# ATMEGA848-S52.net
KiCad netlist of a schematic drawn in Altium Designer
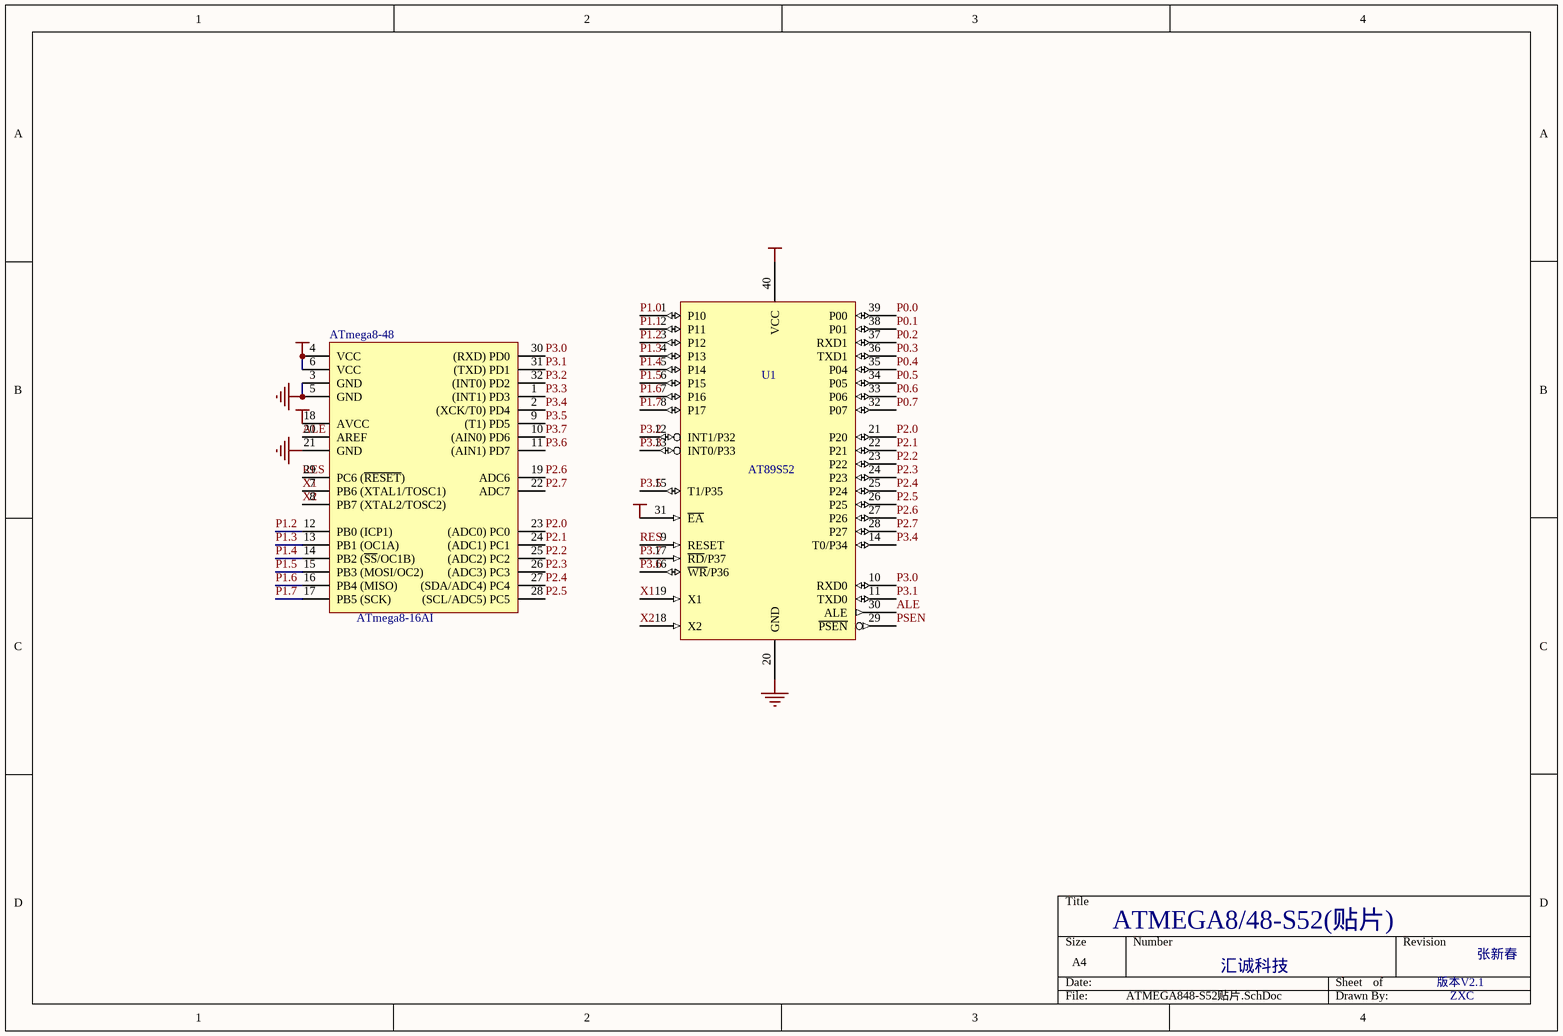
[diagram p0: ATMEGA848-S52贴片.SchDoc]

(export (version "E")
  (design (tool "Eeschema 10.0.6"))
  (components
    (comp (ref "ATmega8-48")
      (value "ATmega8-16AI")
      (footprint "TQFP-32_0.8/7×7mm")
      (description "8 位微处理器/32引脚")
      (fields (field (name "发布者") "磊元工作室"))
      (libsource (lib "微控制处理器") (part "ATmega8-A"))
    )
    (comp (ref "U1") (value "AT89S52") (footprint "DIP-40") (libsource (lib "OldCow1 (2)") (part "8051")))
  )
  (nets
    (net (code "1") (name "/ALE") (class "Default")
      (node (ref "ATmega8-48") (pin "20") (pinfunction "AREF_20") (pintype "passive"))
      (node (ref "U1") (pin "30") (pinfunction "ALE_30") (pintype "output"))
    )
    (net (code "2") (name "/P0.0") (class "Default")
      (node (ref "U1") (pin "39") (pinfunction "P00_39") (pintype "bidirectional"))
    )
    (net (code "3") (name "/P0.1") (class "Default")
      (node (ref "U1") (pin "38") (pinfunction "P01_38") (pintype "bidirectional"))
    )
    (net (code "4") (name "/P0.2") (class "Default")
      (node (ref "U1") (pin "37") (pinfunction "RXD1_37") (pintype "bidirectional"))
    )
    (net (code "5") (name "/P0.3") (class "Default")
      (node (ref "U1") (pin "36") (pinfunction "TXD1_36") (pintype "bidirectional"))
    )
    (net (code "6") (name "/P0.4") (class "Default")
      (node (ref "U1") (pin "35") (pinfunction "P04_35") (pintype "bidirectional"))
    )
    (net (code "7") (name "/P0.5") (class "Default")
      (node (ref "U1") (pin "34") (pinfunction "P05_34") (pintype "bidirectional"))
    )
    (net (code "8") (name "/P0.6") (class "Default")
      (node (ref "U1") (pin "33") (pinfunction "P06_33") (pintype "bidirectional"))
    )
    (net (code "9") (name "/P0.7") (class "Default")
      (node (ref "U1") (pin "32") (pinfunction "P07_32") (pintype "bidirectional"))
    )
    (net (code "10") (name "/P1.0") (class "Default")
      (node (ref "U1") (pin "1") (pinfunction "P10_1") (pintype "bidirectional"))
    )
    (net (code "11") (name "/P1.1") (class "Default")
      (node (ref "U1") (pin "2") (pinfunction "P11_2") (pintype "bidirectional"))
    )
    (net (code "12") (name "/P1.2") (class "Default")
      (node (ref "ATmega8-48") (pin "12") (pinfunction "PB0_(ICP1)_12") (pintype "passive"))
      (node (ref "U1") (pin "3") (pinfunction "P12_3") (pintype "bidirectional"))
    )
    (net (code "13") (name "/P1.3") (class "Default")
      (node (ref "ATmega8-48") (pin "13") (pinfunction "PB1_(OC1A)_13") (pintype "passive"))
      (node (ref "U1") (pin "4") (pinfunction "P13_4") (pintype "bidirectional"))
    )
    (net (code "14") (name "/P1.4") (class "Default")
      (node (ref "ATmega8-48") (pin "14") (pinfunction "PB2_(~{SS}/OC1B)_14") (pintype "passive"))
      (node (ref "U1") (pin "5") (pinfunction "P14_5") (pintype "bidirectional"))
    )
    (net (code "15") (name "/P1.5") (class "Default")
      (node (ref "ATmega8-48") (pin "15") (pinfunction "PB3_(MOSI/OC2)_15") (pintype "passive"))
      (node (ref "U1") (pin "6") (pinfunction "P15_6") (pintype "bidirectional"))
    )
    (net (code "16") (name "/P1.6") (class "Default")
      (node (ref "ATmega8-48") (pin "16") (pinfunction "PB4_(MISO)_16") (pintype "passive"))
      (node (ref "U1") (pin "7") (pinfunction "P16_7") (pintype "bidirectional"))
    )
    (net (code "17") (name "/P1.7") (class "Default")
      (node (ref "ATmega8-48") (pin "17") (pinfunction "PB5_(SCK)_17") (pintype "passive"))
      (node (ref "U1") (pin "8") (pinfunction "P17_8") (pintype "bidirectional"))
    )
    (net (code "18") (name "/P2.0") (class "Default")
      (node (ref "ATmega8-48") (pin "23") (pinfunction "(ADC0)_PC0_23") (pintype "passive"))
      (node (ref "U1") (pin "21") (pinfunction "P20_21") (pintype "bidirectional"))
    )
    (net (code "19") (name "/P2.1") (class "Default")
      (node (ref "ATmega8-48") (pin "24") (pinfunction "(ADC1)_PC1_24") (pintype "passive"))
      (node (ref "U1") (pin "22") (pinfunction "P21_22") (pintype "bidirectional"))
    )
    (net (code "20") (name "/P2.2") (class "Default")
      (node (ref "ATmega8-48") (pin "25") (pinfunction "(ADC2)_PC2_25") (pintype "passive"))
      (node (ref "U1") (pin "23") (pinfunction "P22_23") (pintype "bidirectional"))
    )
    (net (code "21") (name "/P2.3") (class "Default")
      (node (ref "ATmega8-48") (pin "26") (pinfunction "(ADC3)_PC3_26") (pintype "passive"))
      (node (ref "U1") (pin "24") (pinfunction "P23_24") (pintype "bidirectional"))
    )
    (net (code "22") (name "/P2.4") (class "Default")
      (node (ref "ATmega8-48") (pin "27") (pinfunction "(SDA/ADC4)_PC4_27") (pintype "passive"))
      (node (ref "U1") (pin "25") (pinfunction "P24_25") (pintype "bidirectional"))
    )
    (net (code "23") (name "/P2.5") (class "Default")
      (node (ref "ATmega8-48") (pin "28") (pinfunction "(SCL/ADC5)_PC5_28") (pintype "passive"))
      (node (ref "U1") (pin "26") (pinfunction "P25_26") (pintype "bidirectional"))
    )
    (net (code "24") (name "/P2.6") (class "Default")
      (node (ref "ATmega8-48") (pin "19") (pinfunction "ADC6_19") (pintype "passive"))
      (node (ref "U1") (pin "27") (pinfunction "P26_27") (pintype "bidirectional"))
    )
    (net (code "25") (name "/P2.7") (class "Default")
      (node (ref "ATmega8-48") (pin "22") (pinfunction "ADC7_22") (pintype "passive"))
      (node (ref "U1") (pin "28") (pinfunction "P27_28") (pintype "bidirectional"))
    )
    (net (code "26") (name "/P3.0") (class "Default")
      (node (ref "ATmega8-48") (pin "30") (pinfunction "(RXD)_PD0_30") (pintype "passive"))
      (node (ref "U1") (pin "10") (pinfunction "RXD0_10") (pintype "bidirectional"))
    )
    (net (code "27") (name "/P3.1") (class "Default")
      (node (ref "ATmega8-48") (pin "31") (pinfunction "(TXD)_PD1_31") (pintype "passive"))
      (node (ref "U1") (pin "11") (pinfunction "TXD0_11") (pintype "bidirectional"))
    )
    (net (code "28") (name "/P3.2") (class "Default")
      (node (ref "ATmega8-48") (pin "32") (pinfunction "(INT0)_PD2_32") (pintype "passive"))
      (node (ref "U1") (pin "12") (pinfunction "INT1/P32_12") (pintype "bidirectional"))
    )
    (net (code "29") (name "/P3.3") (class "Default")
      (node (ref "ATmega8-48") (pin "1") (pinfunction "(INT1)_PD3_1") (pintype "passive"))
      (node (ref "U1") (pin "13") (pinfunction "INT0/P33_13") (pintype "bidirectional"))
    )
    (net (code "30") (name "/P3.4") (class "Default")
      (node (ref "ATmega8-48") (pin "2") (pinfunction "(XCK/T0)_PD4_2") (pintype "passive"))
      (node (ref "U1") (pin "14") (pinfunction "T0/P34_14") (pintype "bidirectional"))
    )
    (net (code "31") (name "/P3.5") (class "Default")
      (node (ref "ATmega8-48") (pin "9") (pinfunction "(T1)_PD5_9") (pintype "passive"))
      (node (ref "U1") (pin "15") (pinfunction "T1/P35_15") (pintype "bidirectional"))
    )
    (net (code "32") (name "/P3.6") (class "Default")
      (node (ref "ATmega8-48") (pin "11") (pinfunction "(AIN1)_PD7_11") (pintype "passive"))
      (node (ref "U1") (pin "16") (pinfunction "~{WR}/P36_16") (pintype "bidirectional"))
    )
    (net (code "33") (name "/P3.7") (class "Default")
      (node (ref "ATmega8-48") (pin "10") (pinfunction "(AIN0)_PD6_10") (pintype "passive"))
      (node (ref "U1") (pin "17") (pinfunction "~{RD}/P37_17") (pintype "input"))
    )
    (net (code "34") (name "/PSEN") (class "Default")
      (node (ref "U1") (pin "29") (pinfunction "~{PSEN}_29") (pintype "output"))
    )
    (net (code "35") (name "/RES") (class "Default")
      (node (ref "ATmega8-48") (pin "29") (pinfunction "PC6_(~{RESET})_29") (pintype "passive"))
      (node (ref "U1") (pin "9") (pinfunction "RESET_9") (pintype "input"))
    )
    (net (code "36") (name "/X1") (class "Default")
      (node (ref "ATmega8-48") (pin "7") (pinfunction "PB6_(XTAL1/TOSC1)_7") (pintype "passive"))
      (node (ref "U1") (pin "19") (pinfunction "X1_19") (pintype "input"))
    )
    (net (code "37") (name "/X2") (class "Default")
      (node (ref "ATmega8-48") (pin "8") (pinfunction "PB7_(XTAL2/TOSC2)_8") (pintype "passive"))
      (node (ref "U1") (pin "18") (pinfunction "X2_18") (pintype "input"))
    )
    (net (code "38") (name "GND") (class "Default")
      (node (ref "ATmega8-48") (pin "21") (pinfunction "GND_21") (pintype "passive"))
      (node (ref "ATmega8-48") (pin "3") (pinfunction "GND_3") (pintype "passive"))
      (node (ref "ATmega8-48") (pin "5") (pinfunction "GND_5") (pintype "passive"))
      (node (ref "U1") (pin "20") (pinfunction "GND_20") (pintype "power_in"))
    )
    (net (code "39") (name "VCC") (class "Default")
      (node (ref "ATmega8-48") (pin "18") (pinfunction "AVCC_18") (pintype "passive"))
      (node (ref "ATmega8-48") (pin "4") (pinfunction "VCC_4") (pintype "passive"))
      (node (ref "ATmega8-48") (pin "6") (pinfunction "VCC_6") (pintype "passive"))
      (node (ref "U1") (pin "31") (pinfunction "~{EA}_31") (pintype "input"))
      (node (ref "U1") (pin "40") (pinfunction "VCC_40") (pintype "power_in"))
    )
  )
)
